# Sheet2.net
KiCad netlist of a schematic drawn in Altium Designer
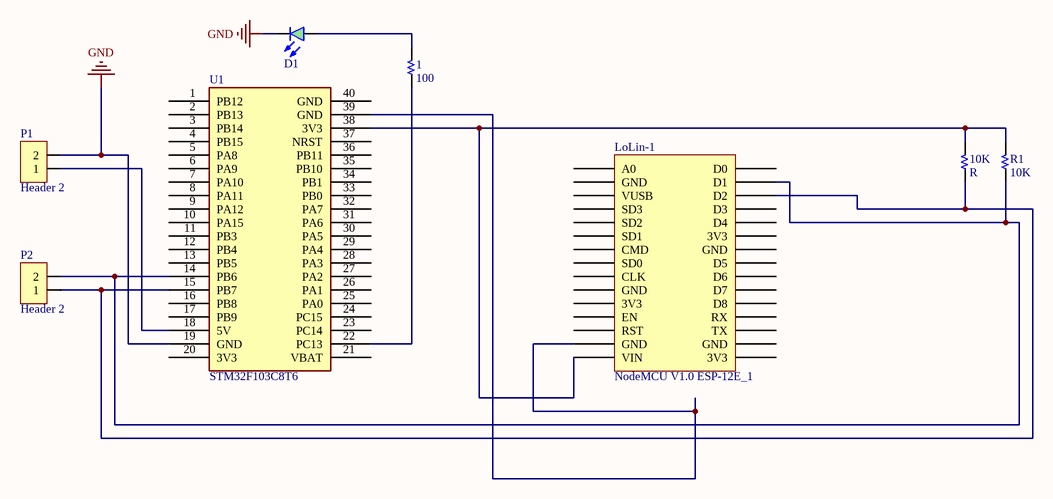
[diagram p0: Sheet2.SchDoc]

(export (version "E")
  (design (tool "Eeschema 10.0.6"))
  (components
    (comp (ref "1")
      (value "100")
      (footprint "R 1/4W/300")
      (description "Resistor")
      (libsource (lib "chipfc_libs") (part "Resistor"))
    )
    (comp (ref "10K")
      (value "R")
      (footprint "R 1/4W/300")
      (description "Resistor")
      (libsource (lib "chipfc_libs") (part "Resistor"))
    )
    (comp (ref "D1")
      (value "LED GREEN")
      (footprint "LED 10MM - GREEN")
      (description "Typical LED 3-pin 2-color")
      (libsource (lib "led") (part "LED GREEN"))
    )
    (comp (ref "LoLin-1")
      (value "NodeMCU V1.0 ESP-12E_1")
      (footprint "LoLin NodeMcu V3")
      (description "LoLin NodeMCU V3")
      (libsource (lib "nodemcu") (part "NodeMCU V1.0 ESP-12E_1"))
    )
    (comp (ref "P1")
      (value "Header 2")
      (footprint "HDR/Terminal/2")
      (description "Header, 2-Pin")
      (libsource (lib "connectors") (part "Header 2"))
    )
    (comp (ref "P2")
      (value "Header 2")
      (footprint "HDR/Header/2")
      (description "Header, 2-Pin")
      (libsource (lib "connectors") (part "Header 2"))
    )
    (comp (ref "R1")
      (value "10K")
      (footprint "R 1/4W/300")
      (description "Resistor")
      (libsource (lib "chipfc_libs") (part "Resistor"))
    )
    (comp (ref "U1")
      (value "STM32F103C8T6")
      (footprint "Stm32 BluePill")
      (description "Designed By @Alixahedi")
      (libsource (lib "Stm32 Blue Pill") (part "BluePill"))
    )
  )
  (nets
    (net (code "1") (name "GND") (class "Default")
      (node (ref "D1") (pin "2") (pinfunction "K_2") (pintype "passive"))
      (node (ref "P1") (pin "2") (pinfunction "2_2") (pintype "passive"))
      (node (ref "U1") (pin "19") (pinfunction "GND_19") (pintype "passive"))
    )
    (net (code "2") (name "Net-(10K-Pad2)") (class "Default")
      (node (ref "10K") (pin "2") (pinfunction "2_2") (pintype "passive"))
      (node (ref "LoLin-1") (pin "VIN") (pinfunction "VIN_VIN") (pintype "passive"))
      (node (ref "R1") (pin "2") (pinfunction "2_2") (pintype "passive"))
      (node (ref "U1") (pin "38") (pinfunction "3V3_38") (pintype "passive"))
    )
    (net (code "3") (name "Net-(D1-A)") (class "Default")
      (node (ref "1") (pin "2") (pinfunction "2_2") (pintype "passive"))
      (node (ref "D1") (pin "1") (pinfunction "A_1") (pintype "passive"))
    )
    (net (code "4") (name "Net-(LoLin-1-PadGND)_1") (class "Default")
      (node (ref "LoLin-1") (pin "GND") (pinfunction "GND_GND") (pintype "passive"))
      (node (ref "U1") (pin "39") (pinfunction "GND_39") (pintype "passive"))
    )
    (net (code "5") (name "Net-(U1-5V)") (class "Default")
      (node (ref "P1") (pin "1") (pinfunction "1_1") (pintype "passive"))
      (node (ref "U1") (pin "18") (pinfunction "5V_18") (pintype "passive"))
    )
    (net (code "6") (name "Net-(U1-PB6)") (class "Default")
      (node (ref "LoLin-1") (pin "D1") (pinfunction "D1_D1") (pintype "passive"))
      (node (ref "P2") (pin "2") (pinfunction "2_2") (pintype "passive"))
      (node (ref "R1") (pin "1") (pinfunction "1_1") (pintype "passive"))
      (node (ref "U1") (pin "14") (pinfunction "PB6_14") (pintype "passive"))
    )
    (net (code "7") (name "Net-(U1-PB7)") (class "Default")
      (node (ref "10K") (pin "1") (pinfunction "1_1") (pintype "passive"))
      (node (ref "LoLin-1") (pin "D2") (pinfunction "D2_D2") (pintype "passive"))
      (node (ref "P2") (pin "1") (pinfunction "1_1") (pintype "passive"))
      (node (ref "U1") (pin "15") (pinfunction "PB7_15") (pintype "passive"))
    )
    (net (code "8") (name "Net-(U1-PC13)") (class "Default")
      (node (ref "1") (pin "1") (pinfunction "1_1") (pintype "passive"))
      (node (ref "U1") (pin "22") (pinfunction "PC13_22") (pintype "passive"))
    )
    (net (code "9") (name "unconnected-(LoLin-1-Pad3V3)") (class "Default")
      (node (ref "LoLin-1") (pin "3V3") (pinfunction "3V3_3V3") (pintype "passive"))
    )
    (net (code "10") (name "unconnected-(LoLin-1-Pad3V3)_1") (class "Default")
      (node (ref "LoLin-1") (pin "3V3") (pinfunction "3V3_3V3") (pintype "passive"))
    )
    (net (code "11") (name "unconnected-(LoLin-1-Pad3V3)_2") (class "Default")
      (node (ref "LoLin-1") (pin "3V3") (pinfunction "3V3_3V3") (pintype "passive"))
    )
    (net (code "12") (name "unconnected-(LoLin-1-PadA0)") (class "Default")
      (node (ref "LoLin-1") (pin "A0") (pinfunction "A0_A0") (pintype "passive"))
    )
    (net (code "13") (name "unconnected-(LoLin-1-PadCLK)") (class "Default")
      (node (ref "LoLin-1") (pin "CLK") (pinfunction "CLK_CLK") (pintype "passive"))
    )
    (net (code "14") (name "unconnected-(LoLin-1-PadCMD)") (class "Default")
      (node (ref "LoLin-1") (pin "CMD") (pinfunction "CMD_CMD") (pintype "passive"))
    )
    (net (code "15") (name "unconnected-(LoLin-1-PadD0)") (class "Default")
      (node (ref "LoLin-1") (pin "D0") (pinfunction "D0_D0") (pintype "passive"))
    )
    (net (code "16") (name "unconnected-(LoLin-1-PadD3)") (class "Default")
      (node (ref "LoLin-1") (pin "D3") (pinfunction "D3_D3") (pintype "passive"))
    )
    (net (code "17") (name "unconnected-(LoLin-1-PadD4)") (class "Default")
      (node (ref "LoLin-1") (pin "D4") (pinfunction "D4_D4") (pintype "passive"))
    )
    (net (code "18") (name "unconnected-(LoLin-1-PadD5)") (class "Default")
      (node (ref "LoLin-1") (pin "D5") (pinfunction "D5_D5") (pintype "passive"))
    )
    (net (code "19") (name "unconnected-(LoLin-1-PadD6)") (class "Default")
      (node (ref "LoLin-1") (pin "D6") (pinfunction "D6_D6") (pintype "passive"))
    )
    (net (code "20") (name "unconnected-(LoLin-1-PadD7)") (class "Default")
      (node (ref "LoLin-1") (pin "D7") (pinfunction "D7_D7") (pintype "passive"))
    )
    (net (code "21") (name "unconnected-(LoLin-1-PadD8)") (class "Default")
      (node (ref "LoLin-1") (pin "D8") (pinfunction "D8_D8") (pintype "passive"))
    )
    (net (code "22") (name "unconnected-(LoLin-1-PadEN)") (class "Default")
      (node (ref "LoLin-1") (pin "EN") (pinfunction "EN_EN") (pintype "passive"))
    )
    (net (code "23") (name "unconnected-(LoLin-1-PadGND)") (class "Default")
      (node (ref "LoLin-1") (pin "GND") (pinfunction "GND_GND") (pintype "passive"))
    )
    (net (code "24") (name "unconnected-(LoLin-1-PadGND)_2") (class "Default")
      (node (ref "LoLin-1") (pin "GND") (pinfunction "GND_GND") (pintype "passive"))
    )
    (net (code "25") (name "unconnected-(LoLin-1-PadGND)_3") (class "Default")
      (node (ref "LoLin-1") (pin "GND") (pinfunction "GND_GND") (pintype "passive"))
    )
    (net (code "26") (name "unconnected-(LoLin-1-PadGND)_4") (class "Default")
      (node (ref "LoLin-1") (pin "GND") (pinfunction "GND_GND") (pintype "passive"))
    )
    (net (code "27") (name "unconnected-(LoLin-1-PadRST)") (class "Default")
      (node (ref "LoLin-1") (pin "RST") (pinfunction "RST_RST") (pintype "passive"))
    )
    (net (code "28") (name "unconnected-(LoLin-1-PadRX)") (class "Default")
      (node (ref "LoLin-1") (pin "RX") (pinfunction "RX_RX") (pintype "passive"))
    )
    (net (code "29") (name "unconnected-(LoLin-1-PadSD0)") (class "Default")
      (node (ref "LoLin-1") (pin "SD0") (pinfunction "SD0_SD0") (pintype "passive"))
    )
    (net (code "30") (name "unconnected-(LoLin-1-PadSD1)") (class "Default")
      (node (ref "LoLin-1") (pin "SD1") (pinfunction "SD1_SD1") (pintype "passive"))
    )
    (net (code "31") (name "unconnected-(LoLin-1-PadSD2)") (class "Default")
      (node (ref "LoLin-1") (pin "SD2") (pinfunction "SD2_SD2") (pintype "passive"))
    )
    (net (code "32") (name "unconnected-(LoLin-1-PadSD3)") (class "Default")
      (node (ref "LoLin-1") (pin "SD3") (pinfunction "SD3_SD3") (pintype "passive"))
    )
    (net (code "33") (name "unconnected-(LoLin-1-PadTX)") (class "Default")
      (node (ref "LoLin-1") (pin "TX") (pinfunction "TX_TX") (pintype "passive"))
    )
    (net (code "34") (name "unconnected-(LoLin-1-PadVUSB)") (class "Default")
      (node (ref "LoLin-1") (pin "VUSB") (pinfunction "VUSB_VUSB") (pintype "passive"))
    )
    (net (code "35") (name "unconnected-(U1-3V3-Pad20)") (class "Default")
      (node (ref "U1") (pin "20") (pinfunction "3V3_20") (pintype "passive"))
    )
    (net (code "36") (name "unconnected-(U1-GND-Pad40)") (class "Default")
      (node (ref "U1") (pin "40") (pinfunction "GND_40") (pintype "passive"))
    )
    (net (code "37") (name "unconnected-(U1-NRST-Pad37)") (class "Default")
      (node (ref "U1") (pin "37") (pinfunction "NRST_37") (pintype "passive"))
    )
    (net (code "38") (name "unconnected-(U1-PA0-Pad25)") (class "Default")
      (node (ref "U1") (pin "25") (pinfunction "PA0_25") (pintype "passive"))
    )
    (net (code "39") (name "unconnected-(U1-PA1-Pad26)") (class "Default")
      (node (ref "U1") (pin "26") (pinfunction "PA1_26") (pintype "passive"))
    )
    (net (code "40") (name "unconnected-(U1-PA2-Pad27)") (class "Default")
      (node (ref "U1") (pin "27") (pinfunction "PA2_27") (pintype "passive"))
    )
    (net (code "41") (name "unconnected-(U1-PA3-Pad28)") (class "Default")
      (node (ref "U1") (pin "28") (pinfunction "PA3_28") (pintype "passive"))
    )
    (net (code "42") (name "unconnected-(U1-PA4-Pad29)") (class "Default")
      (node (ref "U1") (pin "29") (pinfunction "PA4_29") (pintype "passive"))
    )
    (net (code "43") (name "unconnected-(U1-PA5-Pad30)") (class "Default")
      (node (ref "U1") (pin "30") (pinfunction "PA5_30") (pintype "passive"))
    )
    (net (code "44") (name "unconnected-(U1-PA6-Pad31)") (class "Default")
      (node (ref "U1") (pin "31") (pinfunction "PA6_31") (pintype "passive"))
    )
    (net (code "45") (name "unconnected-(U1-PA7-Pad32)") (class "Default")
      (node (ref "U1") (pin "32") (pinfunction "PA7_32") (pintype "passive"))
    )
    (net (code "46") (name "unconnected-(U1-PA8-Pad5)") (class "Default")
      (node (ref "U1") (pin "5") (pinfunction "PA8_5") (pintype "passive"))
    )
    (net (code "47") (name "unconnected-(U1-PA9-Pad6)") (class "Default")
      (node (ref "U1") (pin "6") (pinfunction "PA9_6") (pintype "passive"))
    )
    (net (code "48") (name "unconnected-(U1-PA10-Pad7)") (class "Default")
      (node (ref "U1") (pin "7") (pinfunction "PA10_7") (pintype "passive"))
    )
    (net (code "49") (name "unconnected-(U1-PA11-Pad8)") (class "Default")
      (node (ref "U1") (pin "8") (pinfunction "PA11_8") (pintype "passive"))
    )
    (net (code "50") (name "unconnected-(U1-PA12-Pad9)") (class "Default")
      (node (ref "U1") (pin "9") (pinfunction "PA12_9") (pintype "passive"))
    )
    (net (code "51") (name "unconnected-(U1-PA15-Pad10)") (class "Default")
      (node (ref "U1") (pin "10") (pinfunction "PA15_10") (pintype "passive"))
    )
    (net (code "52") (name "unconnected-(U1-PB0-Pad33)") (class "Default")
      (node (ref "U1") (pin "33") (pinfunction "PB0_33") (pintype "passive"))
    )
    (net (code "53") (name "unconnected-(U1-PB1-Pad34)") (class "Default")
      (node (ref "U1") (pin "34") (pinfunction "PB1_34") (pintype "passive"))
    )
    (net (code "54") (name "unconnected-(U1-PB3-Pad11)") (class "Default")
      (node (ref "U1") (pin "11") (pinfunction "PB3_11") (pintype "passive"))
    )
    (net (code "55") (name "unconnected-(U1-PB4-Pad12)") (class "Default")
      (node (ref "U1") (pin "12") (pinfunction "PB4_12") (pintype "passive"))
    )
    (net (code "56") (name "unconnected-(U1-PB5-Pad13)") (class "Default")
      (node (ref "U1") (pin "13") (pinfunction "PB5_13") (pintype "passive"))
    )
    (net (code "57") (name "unconnected-(U1-PB8-Pad16)") (class "Default")
      (node (ref "U1") (pin "16") (pinfunction "PB8_16") (pintype "passive"))
    )
    (net (code "58") (name "unconnected-(U1-PB9-Pad17)") (class "Default")
      (node (ref "U1") (pin "17") (pinfunction "PB9_17") (pintype "passive"))
    )
    (net (code "59") (name "unconnected-(U1-PB10-Pad35)") (class "Default")
      (node (ref "U1") (pin "35") (pinfunction "PB10_35") (pintype "passive"))
    )
    (net (code "60") (name "unconnected-(U1-PB11-Pad36)") (class "Default")
      (node (ref "U1") (pin "36") (pinfunction "PB11_36") (pintype "passive"))
    )
    (net (code "61") (name "unconnected-(U1-PB12-Pad1)") (class "Default")
      (node (ref "U1") (pin "1") (pinfunction "PB12_1") (pintype "passive"))
    )
    (net (code "62") (name "unconnected-(U1-PB13-Pad2)") (class "Default")
      (node (ref "U1") (pin "2") (pinfunction "PB13_2") (pintype "passive"))
    )
    (net (code "63") (name "unconnected-(U1-PB14-Pad3)") (class "Default")
      (node (ref "U1") (pin "3") (pinfunction "PB14_3") (pintype "passive"))
    )
    (net (code "64") (name "unconnected-(U1-PB15-Pad4)") (class "Default")
      (node (ref "U1") (pin "4") (pinfunction "PB15_4") (pintype "passive"))
    )
    (net (code "65") (name "unconnected-(U1-PC14-Pad23)") (class "Default")
      (node (ref "U1") (pin "23") (pinfunction "PC14_23") (pintype "passive"))
    )
    (net (code "66") (name "unconnected-(U1-PC15-Pad24)") (class "Default")
      (node (ref "U1") (pin "24") (pinfunction "PC15_24") (pintype "passive"))
    )
    (net (code "67") (name "unconnected-(U1-VBAT-Pad21)") (class "Default")
      (node (ref "U1") (pin "21") (pinfunction "VBAT_21") (pintype "passive"))
    )
  )
)
